# MOSFETS.net
KiCad netlist of a schematic drawn in Altium Designer
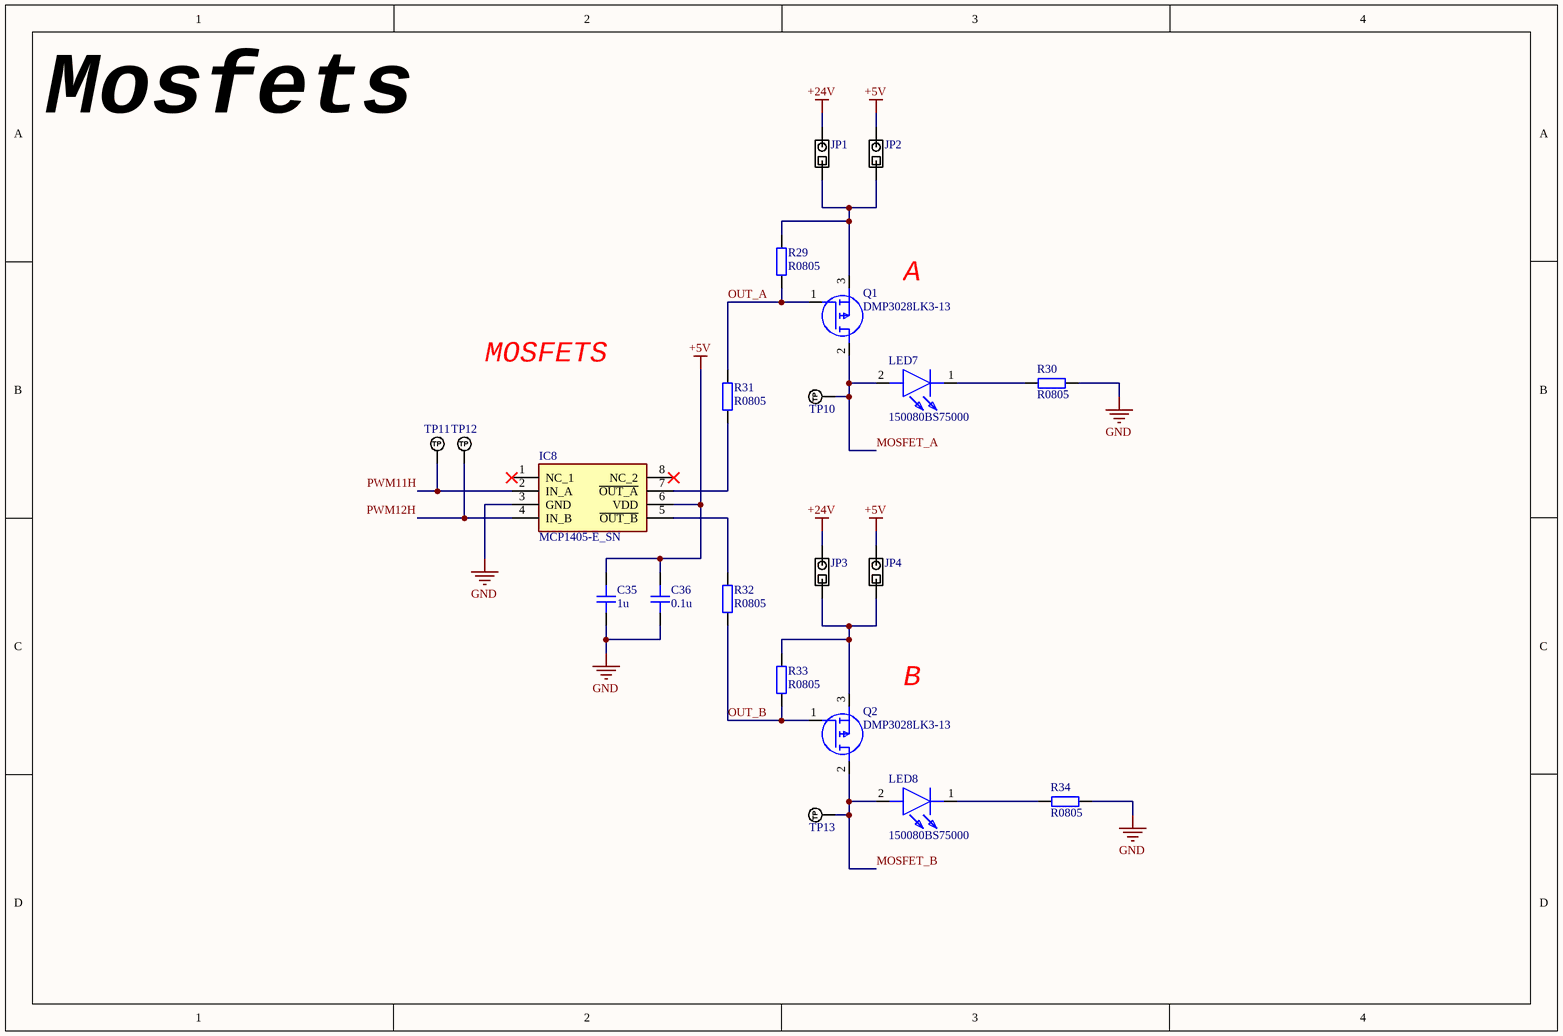
[diagram p0: MOSFETS.SchDoc]

(export (version "E")
  (design (tool "Eeschema 10.0.6"))
  (components
    (comp (ref "C35")
      (value "1u")
      (footprint "CAP_0805")
      (description "Capacitor SMD 0805 10V")
      (libsource (lib "Schematic-Lib-PhilsLab") (part "CAP_0805_10V"))
    )
    (comp (ref "C36")
      (value "0.1u")
      (footprint "CAP_0805")
      (description "Capacitor SMD 0805 10V")
      (libsource (lib "Schematic-Lib-PhilsLab") (part "CAP_0805_10V"))
    )
    (comp (ref "IC8")
      (value "MCP1405-E_SN")
      (footprint "SOIC127P600X175-8N")
      (description "Integrated Circuit")
      (fields
        (field (name "MANUFACTURER_PART_NUMBER") "MCP1405-E/SN")
        (field (name "MOUSER PART NUMBER") "579-MCP1405-E/SN")
      )
      (libsource (lib "Pedro_Integrated_Library") (part "MCP1405-E_SN"))
    )
    (comp (ref "JP1")
      (value "Solder Jumper")
      (footprint "SolderJumper_Single")
      (description "Solder Jumper Single 0.5mm Pitch")
      (libsource (lib "Pedro_Integrated_Library") (part "SolderJumper_Single"))
    )
    (comp (ref "JP2")
      (value "Solder Jumper")
      (footprint "SolderJumper_Single")
      (description "Solder Jumper Single 0.5mm Pitch")
      (libsource (lib "Pedro_Integrated_Library") (part "SolderJumper_Single"))
    )
    (comp (ref "JP3")
      (value "Solder Jumper")
      (footprint "SolderJumper_Single")
      (description "Solder Jumper Single 0.5mm Pitch")
      (libsource (lib "Pedro_Integrated_Library") (part "SolderJumper_Single"))
    )
    (comp (ref "JP4")
      (value "Solder Jumper")
      (footprint "SolderJumper_Single")
      (description "Solder Jumper Single 0.5mm Pitch")
      (libsource (lib "Pedro_Integrated_Library") (part "SolderJumper_Single"))
    )
    (comp (ref "LED7")
      (value "150080BS75000")
      (footprint "LEDC2012X80N")
      (description "LED")
      (fields (field (name "MOUSER PART NUMBER") "710-150080BS75000"))
      (libsource (lib "Pedro_Integrated_Library") (part "150080BS75000"))
    )
    (comp (ref "LED8")
      (value "150080BS75000")
      (footprint "LEDC2012X80N")
      (description "LED")
      (fields (field (name "MOUSER PART NUMBER") "710-150080BS75000"))
      (libsource (lib "Pedro_Integrated_Library") (part "150080BS75000"))
    )
    (comp (ref "Q1")
      (value "DMP3028LK3-13")
      (footprint "DMP3028LK313")
      (description "MOSFET (P-Channel)")
      (fields (field (name "MOUSER PART NUMBER") "621-DMP3028LK3-13"))
      (libsource (lib "Pedro_Integrated_Library") (part "DMP3028LK3-13"))
    )
    (comp (ref "Q2")
      (value "DMP3028LK3-13")
      (footprint "DMP3028LK313")
      (description "MOSFET (P-Channel)")
      (fields (field (name "MOUSER PART NUMBER") "621-DMP3028LK3-13"))
      (libsource (lib "Pedro_Integrated_Library") (part "DMP3028LK3-13"))
    )
    (comp (ref "R29")
      (value "R0805")
      (footprint "RES_0805")
      (description "Resistor SMD 0805")
      (libsource (lib "Pedro_Integrated_Library") (part "RES_0805"))
    )
    (comp (ref "R30")
      (value "R0805")
      (footprint "RES_0805")
      (description "Resistor SMD 0805")
      (libsource (lib "Pedro_Integrated_Library") (part "RES_0805"))
    )
    (comp (ref "R31")
      (value "R0805")
      (footprint "RES_0805")
      (description "Resistor SMD 0805")
      (libsource (lib "Pedro_Integrated_Library") (part "RES_0805"))
    )
    (comp (ref "R32")
      (value "R0805")
      (footprint "RES_0805")
      (description "Resistor SMD 0805")
      (libsource (lib "Pedro_Integrated_Library") (part "RES_0805"))
    )
    (comp (ref "R33")
      (value "R0805")
      (footprint "RES_0805")
      (description "Resistor SMD 0805")
      (libsource (lib "Pedro_Integrated_Library") (part "RES_0805"))
    )
    (comp (ref "R34")
      (value "R0805")
      (footprint "RES_0805")
      (description "Resistor SMD 0805")
      (libsource (lib "Pedro_Integrated_Library") (part "RES_0805"))
    )
    (comp (ref "TP10")
      (value "TP_NOBOM")
      (footprint "PAD_RND_1MM")
      (description "Test Point Round 1mm (NO BOM)")
      (libsource (lib "Schematic-Lib-PhilsLab") (part "TEST_POINT_RND_1MM"))
    )
    (comp (ref "TP11")
      (value "TP_NOBOM")
      (footprint "PAD_RND_1MM")
      (description "Test Point Round 1mm (NO BOM)")
      (libsource (lib "Schematic-Lib-PhilsLab") (part "TEST_POINT_RND_1MM"))
    )
    (comp (ref "TP12")
      (value "TP_NOBOM")
      (footprint "PAD_RND_1MM")
      (description "Test Point Round 1mm (NO BOM)")
      (libsource (lib "Schematic-Lib-PhilsLab") (part "TEST_POINT_RND_1MM"))
    )
    (comp (ref "TP13")
      (value "TP_NOBOM")
      (footprint "PAD_RND_1MM")
      (description "Test Point Round 1mm (NO BOM)")
      (libsource (lib "Schematic-Lib-PhilsLab") (part "TEST_POINT_RND_1MM"))
    )
  )
  (nets
    (net (code "1") (name "+5V") (class "Default")
      (node (ref "C35") (pin "2") (pinfunction "2_2") (pintype "passive"))
      (node (ref "C36") (pin "2") (pinfunction "2_2") (pintype "passive"))
      (node (ref "IC8") (pin "6") (pinfunction "VDD_6") (pintype "passive"))
      (node (ref "JP2") (pin "2") (pinfunction "2_2") (pintype "passive"))
      (node (ref "JP4") (pin "2") (pinfunction "2_2") (pintype "passive"))
    )
    (net (code "2") (name "+24V") (class "Default")
      (node (ref "JP1") (pin "2") (pinfunction "2_2") (pintype "passive"))
      (node (ref "JP3") (pin "2") (pinfunction "2_2") (pintype "passive"))
    )
    (net (code "3") (name "/MOSFET_A") (class "Default")
      (node (ref "LED7") (pin "2") (pinfunction "A_2") (pintype "passive"))
      (node (ref "Q1") (pin "2") (pinfunction "D_2") (pintype "passive"))
      (node (ref "TP10") (pin "1") (pinfunction "TP_1") (pintype "passive"))
    )
    (net (code "4") (name "/MOSFET_B") (class "Default")
      (node (ref "LED8") (pin "2") (pinfunction "A_2") (pintype "passive"))
      (node (ref "Q2") (pin "2") (pinfunction "D_2") (pintype "passive"))
      (node (ref "TP13") (pin "1") (pinfunction "TP_1") (pintype "passive"))
    )
    (net (code "5") (name "/OUT_A") (class "Default")
      (node (ref "Q1") (pin "1") (pinfunction "G_1") (pintype "passive"))
      (node (ref "R29") (pin "1") (pinfunction "1_1") (pintype "passive"))
      (node (ref "R31") (pin "2") (pinfunction "2_2") (pintype "passive"))
    )
    (net (code "6") (name "/OUT_B") (class "Default")
      (node (ref "Q2") (pin "1") (pinfunction "G_1") (pintype "passive"))
      (node (ref "R32") (pin "1") (pinfunction "1_1") (pintype "passive"))
      (node (ref "R33") (pin "1") (pinfunction "1_1") (pintype "passive"))
    )
    (net (code "7") (name "/PWM11H") (class "Default")
      (node (ref "IC8") (pin "2") (pinfunction "IN_A_2") (pintype "passive"))
      (node (ref "TP11") (pin "1") (pinfunction "TP_1") (pintype "passive"))
    )
    (net (code "8") (name "/PWM12H") (class "Default")
      (node (ref "IC8") (pin "4") (pinfunction "IN_B_4") (pintype "passive"))
      (node (ref "TP12") (pin "1") (pinfunction "TP_1") (pintype "passive"))
    )
    (net (code "9") (name "GND") (class "Default")
      (node (ref "C35") (pin "1") (pinfunction "1_1") (pintype "passive"))
      (node (ref "C36") (pin "1") (pinfunction "1_1") (pintype "passive"))
      (node (ref "IC8") (pin "3") (pinfunction "GND_3") (pintype "passive"))
      (node (ref "R30") (pin "1") (pinfunction "1_1") (pintype "passive"))
      (node (ref "R34") (pin "1") (pinfunction "1_1") (pintype "passive"))
    )
    (net (code "10") (name "Net-(IC8-~{OUT_A})") (class "Default")
      (node (ref "IC8") (pin "7") (pinfunction "~{OUT_A}_7") (pintype "passive"))
      (node (ref "R31") (pin "1") (pinfunction "1_1") (pintype "passive"))
    )
    (net (code "11") (name "Net-(IC8-~{OUT_B})") (class "Default")
      (node (ref "IC8") (pin "5") (pinfunction "~{OUT_B}_5") (pintype "passive"))
      (node (ref "R32") (pin "2") (pinfunction "2_2") (pintype "passive"))
    )
    (net (code "12") (name "Net-(LED7-K)") (class "Default")
      (node (ref "LED7") (pin "1") (pinfunction "K_1") (pintype "passive"))
      (node (ref "R30") (pin "2") (pinfunction "2_2") (pintype "passive"))
    )
    (net (code "13") (name "Net-(LED8-K)") (class "Default")
      (node (ref "LED8") (pin "1") (pinfunction "K_1") (pintype "passive"))
      (node (ref "R34") (pin "2") (pinfunction "2_2") (pintype "passive"))
    )
    (net (code "14") (name "Net-(Q1-S)") (class "Default")
      (node (ref "JP1") (pin "1") (pinfunction "1_1") (pintype "passive"))
      (node (ref "JP2") (pin "1") (pinfunction "1_1") (pintype "passive"))
      (node (ref "Q1") (pin "3") (pinfunction "S_3") (pintype "passive"))
      (node (ref "R29") (pin "2") (pinfunction "2_2") (pintype "passive"))
    )
    (net (code "15") (name "Net-(Q2-S)") (class "Default")
      (node (ref "JP3") (pin "1") (pinfunction "1_1") (pintype "passive"))
      (node (ref "JP4") (pin "1") (pinfunction "1_1") (pintype "passive"))
      (node (ref "Q2") (pin "3") (pinfunction "S_3") (pintype "passive"))
      (node (ref "R33") (pin "2") (pinfunction "2_2") (pintype "passive"))
    )
    (net (code "16") (name "unconnected-(IC8-NC_1-Pad1)") (class "Default")
      (node (ref "IC8") (pin "1") (pinfunction "NC_1_1") (pintype "passive+no_connect"))
    )
    (net (code "17") (name "unconnected-(IC8-NC_2-Pad8)") (class "Default")
      (node (ref "IC8") (pin "8") (pinfunction "NC_2_8") (pintype "passive+no_connect"))
    )
  )
)
